# Sheet1.net
KiCad netlist of a schematic drawn in Altium Designer
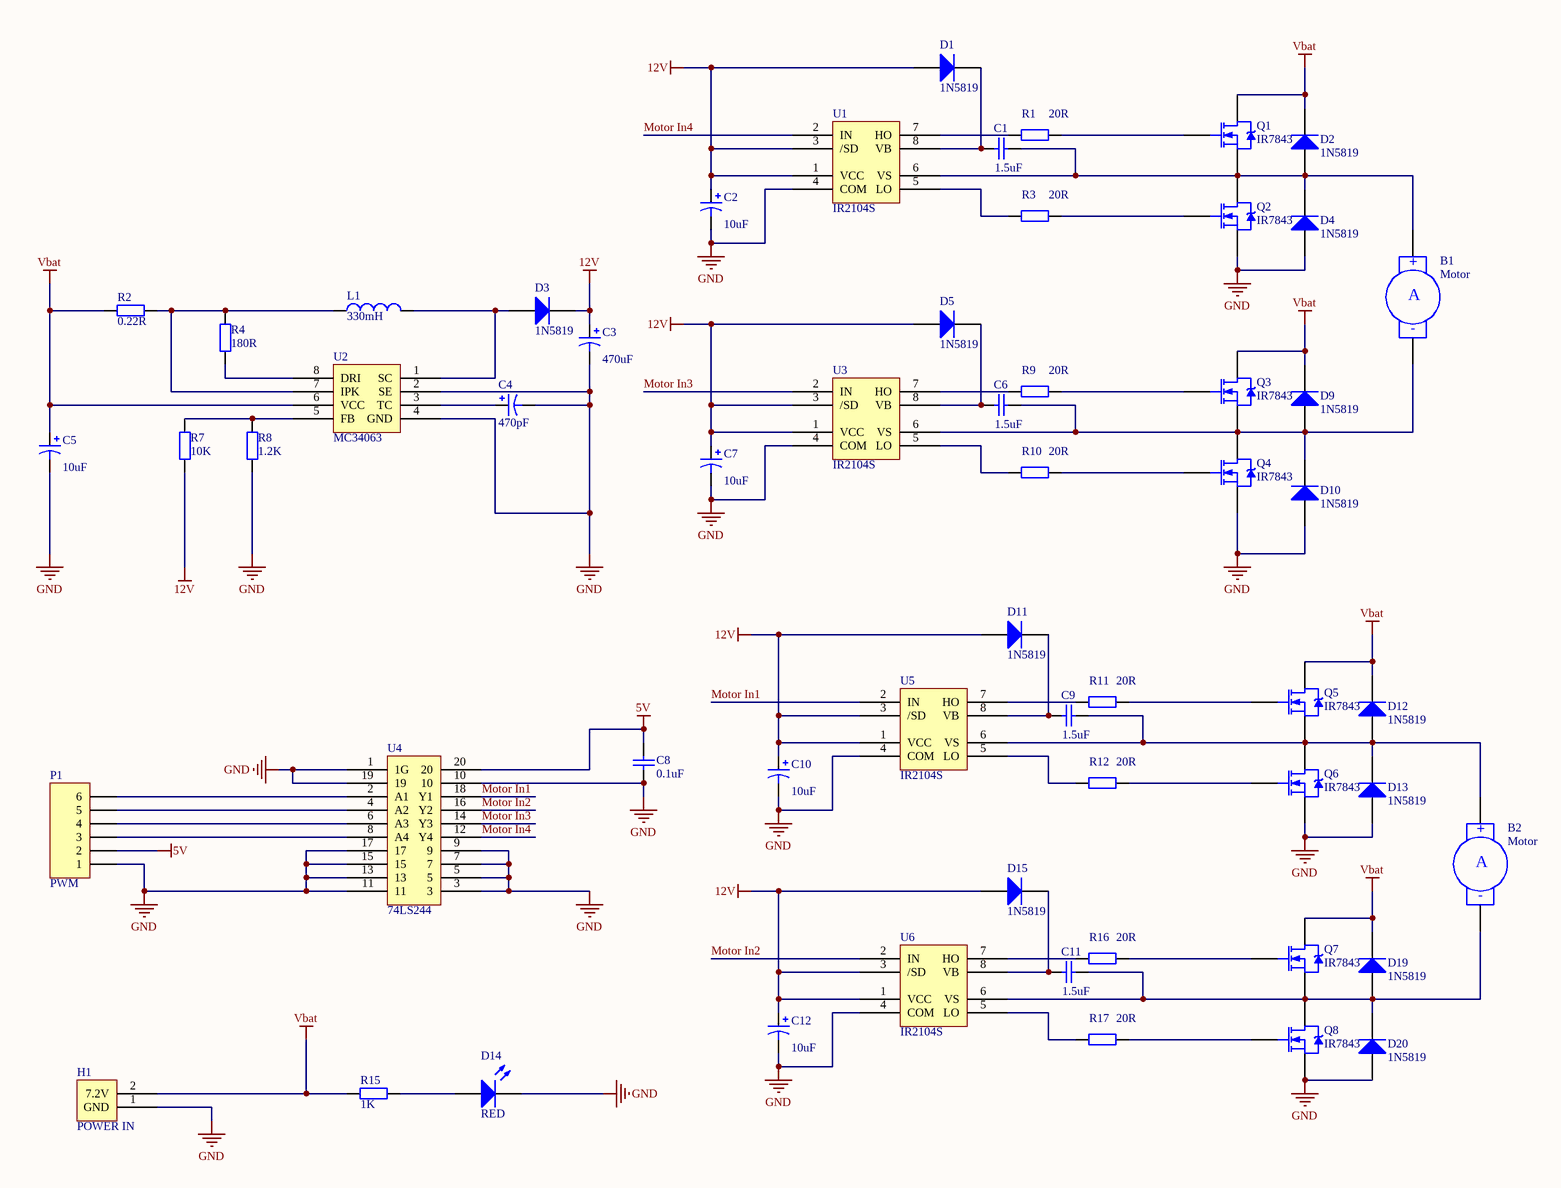
[diagram p0: Sheet1.SchDoc]

(export (version "E")
  (design (tool "Eeschema 10.0.6"))
  (components
    (comp (ref "B1")
      (value "Motor")
      (footprint "KF301-2P")
      (description "Servo Motor")
      (fields (field (name "PUBLISHER") "Altium Limited"))
      (libsource (lib "Miscellaneous Devices") (part "Motor Servo"))
    )
    (comp (ref "B2")
      (value "Motor")
      (footprint "KF301-2P")
      (description "Servo Motor")
      (fields (field (name "PUBLISHER") "Altium Limited"))
      (libsource (lib "Miscellaneous Devices") (part "Motor Servo"))
    )
    (comp (ref "C1")
      (value "1.5uF")
      (footprint "0805(2012)")
      (description "Capacitor")
      (fields (field (name "Comment") "Cap") (field (name "PUBLISHER") "Altium Limited"))
      (libsource (lib "Miscellaneous Devices") (part "Cap"))
    )
    (comp (ref "C2")
      (value "10uF")
      (footprint "SOD-323(0805)")
      (description "Polarized Capacitor (Radial)")
      (fields (field (name "Comment") "Cap Pol1") (field (name "PUBLISHER") "Altium Limited"))
      (libsource (lib "Miscellaneous Devices") (part "Cap Pol1"))
    )
    (comp (ref "C3")
      (value "470uF")
      (footprint "RB5-10.5")
      (description "Polarized Capacitor (Radial)")
      (fields (field (name "Comment") "Cap Pol1") (field (name "PUBLISHER") "Altium Limited"))
      (libsource (lib "Miscellaneous Devices") (part "Cap Pol1"))
    )
    (comp (ref "C4")
      (value "470pF")
      (footprint "SOD-323(0805)")
      (description "Polarized Capacitor (Radial)")
      (fields (field (name "Comment") "Cap Pol1") (field (name "PUBLISHER") "Altium Limited"))
      (libsource (lib "Miscellaneous Devices") (part "Cap Pol1"))
    )
    (comp (ref "C5")
      (value "10uF")
      (footprint "SOD-323(0805)")
      (description "Polarized Capacitor (Radial)")
      (fields (field (name "Comment") "Cap Pol1") (field (name "PUBLISHER") "Altium Limited"))
      (libsource (lib "Miscellaneous Devices") (part "Cap Pol1"))
    )
    (comp (ref "C6")
      (value "1.5uF")
      (footprint "0805(2012)")
      (description "Capacitor")
      (fields (field (name "Comment") "Cap") (field (name "PUBLISHER") "Altium Limited"))
      (libsource (lib "Miscellaneous Devices") (part "Cap"))
    )
    (comp (ref "C7")
      (value "10uF")
      (footprint "SOD-323(0805)")
      (description "Polarized Capacitor (Radial)")
      (fields (field (name "Comment") "Cap Pol1") (field (name "PUBLISHER") "Altium Limited"))
      (libsource (lib "Miscellaneous Devices") (part "Cap Pol1"))
    )
    (comp (ref "C8")
      (value "0.1uF")
      (footprint "0805(2012)")
      (description "Capacitor")
      (fields (field (name "Comment") "Cap") (field (name "PUBLISHER") "Altium Limited"))
      (libsource (lib "LY") (part "Cap"))
    )
    (comp (ref "C9")
      (value "1.5uF")
      (footprint "0805(2012)")
      (description "Capacitor")
      (fields (field (name "Comment") "Cap") (field (name "PUBLISHER") "Altium Limited"))
      (libsource (lib "Miscellaneous Devices") (part "Cap"))
    )
    (comp (ref "C10")
      (value "10uF")
      (footprint "SOD-323(0805)")
      (description "Polarized Capacitor (Radial)")
      (fields (field (name "Comment") "Cap Pol1") (field (name "PUBLISHER") "Altium Limited"))
      (libsource (lib "Miscellaneous Devices") (part "Cap Pol1"))
    )
    (comp (ref "C11")
      (value "1.5uF")
      (footprint "0805(2012)")
      (description "Capacitor")
      (fields (field (name "Comment") "Cap") (field (name "PUBLISHER") "Altium Limited"))
      (libsource (lib "Miscellaneous Devices") (part "Cap"))
    )
    (comp (ref "C12")
      (value "10uF")
      (footprint "SOD-323(0805)")
      (description "Polarized Capacitor (Radial)")
      (fields (field (name "Comment") "Cap Pol1") (field (name "PUBLISHER") "Altium Limited"))
      (libsource (lib "Miscellaneous Devices") (part "Cap Pol1"))
    )
    (comp (ref "D1")
      (value "1N5819")
      (footprint "0805(2012)")
      (description "Silicon Epitaxial Planar Diode for Various Detector, Modulator, Demodulator")
      (fields (field (name "PUBLISHER") "Altium Limited"))
      (libsource (lib "Renesas Diode") (part "1N4148"))
    )
    (comp (ref "D2")
      (value "1N5819")
      (footprint "0805(2012)")
      (description "Silicon Epitaxial Planar Diode for Various Detector, Modulator, Demodulator")
      (fields (field (name "PUBLISHER") "Altium Limited"))
      (libsource (lib "Renesas Diode") (part "1N4148"))
    )
    (comp (ref "D3")
      (value "1N5819")
      (footprint "0805(2012)")
      (description "Silicon Epitaxial Planar Diode for Various Detector, Modulator, Demodulator")
      (fields (field (name "PUBLISHER") "Altium Limited"))
      (libsource (lib "Renesas Diode") (part "1N4148"))
    )
    (comp (ref "D4")
      (value "1N5819")
      (footprint "0805(2012)")
      (description "Silicon Epitaxial Planar Diode for Various Detector, Modulator, Demodulator")
      (fields (field (name "PUBLISHER") "Altium Limited"))
      (libsource (lib "Renesas Diode") (part "1N4148"))
    )
    (comp (ref "D5")
      (value "1N5819")
      (footprint "0805(2012)")
      (description "Silicon Epitaxial Planar Diode for Various Detector, Modulator, Demodulator")
      (fields (field (name "PUBLISHER") "Altium Limited"))
      (libsource (lib "Renesas Diode") (part "1N4148"))
    )
    (comp (ref "D9")
      (value "1N5819")
      (footprint "0805(2012)")
      (description "Silicon Epitaxial Planar Diode for Various Detector, Modulator, Demodulator")
      (fields (field (name "PUBLISHER") "Altium Limited"))
      (libsource (lib "Renesas Diode") (part "1N4148"))
    )
    (comp (ref "D10")
      (value "1N5819")
      (footprint "0805(2012)")
      (description "Silicon Epitaxial Planar Diode for Various Detector, Modulator, Demodulator")
      (fields (field (name "PUBLISHER") "Altium Limited"))
      (libsource (lib "Renesas Diode") (part "1N4148"))
    )
    (comp (ref "D11")
      (value "1N5819")
      (footprint "0805(2012)")
      (description "Silicon Epitaxial Planar Diode for Various Detector, Modulator, Demodulator")
      (fields (field (name "PUBLISHER") "Altium Limited"))
      (libsource (lib "Renesas Diode") (part "1N4148"))
    )
    (comp (ref "D12")
      (value "1N5819")
      (footprint "0805(2012)")
      (description "Silicon Epitaxial Planar Diode for Various Detector, Modulator, Demodulator")
      (fields (field (name "PUBLISHER") "Altium Limited"))
      (libsource (lib "Renesas Diode") (part "1N4148"))
    )
    (comp (ref "D13")
      (value "1N5819")
      (footprint "0805(2012)")
      (description "Silicon Epitaxial Planar Diode for Various Detector, Modulator, Demodulator")
      (fields (field (name "PUBLISHER") "Altium Limited"))
      (libsource (lib "Renesas Diode") (part "1N4148"))
    )
    (comp (ref "D14")
      (value "RED")
      (footprint "0805LED")
      (description "Typical RED, GREEN, YELLOW, AMBER GaAs LED")
      (fields (field (name "PUBLISHER") "Altium Limited"))
      (libsource (lib "LY") (part "LED2"))
    )
    (comp (ref "D15")
      (value "1N5819")
      (footprint "0805(2012)")
      (description "Silicon Epitaxial Planar Diode for Various Detector, Modulator, Demodulator")
      (fields (field (name "PUBLISHER") "Altium Limited"))
      (libsource (lib "Renesas Diode") (part "1N4148"))
    )
    (comp (ref "D19")
      (value "1N5819")
      (footprint "0805(2012)")
      (description "Silicon Epitaxial Planar Diode for Various Detector, Modulator, Demodulator")
      (fields (field (name "PUBLISHER") "Altium Limited"))
      (libsource (lib "Renesas Diode") (part "1N4148"))
    )
    (comp (ref "D20")
      (value "1N5819")
      (footprint "0805(2012)")
      (description "Silicon Epitaxial Planar Diode for Various Detector, Modulator, Demodulator")
      (fields (field (name "PUBLISHER") "Altium Limited"))
      (libsource (lib "Renesas Diode") (part "1N4148"))
    )
    (comp (ref "H1")
      (value "POWER IN")
      (footprint "KF301-2P")
      (libsource (lib "MOS motor") (part "POWER IN"))
    )
    (comp (ref "L1")
      (value "330mH")
      (footprint "电感10*12")
      (description "Inductor")
      (fields (field (name "PUBLISHER") "Altium Limited"))
      (libsource (lib "Miscellaneous Devices") (part "Inductor"))
    )
    (comp (ref "P1")
      (value "PWM")
      (footprint "HDR1X6")
      (description "Header, 6-Pin")
      (fields (field (name "PUBLISHER") "Altium Limited"))
      (libsource (lib "Miscellaneous Connectors") (part "Header 6"))
    )
    (comp (ref "Q1")
      (value "IR7843")
      (footprint "LR7843")
      (description "N-Channel Power MOSFET")
      (fields (field (name "PUBLISHER") "Altium Limited"))
      (libsource (lib "PowerIn") (part "IR7843"))
    )
    (comp (ref "Q2")
      (value "IR7843")
      (footprint "LR7843")
      (description "N-Channel Power MOSFET")
      (fields (field (name "PUBLISHER") "Altium Limited"))
      (libsource (lib "PowerIn") (part "IR7843"))
    )
    (comp (ref "Q3")
      (value "IR7843")
      (footprint "LR7843")
      (description "N-Channel Power MOSFET")
      (fields (field (name "PUBLISHER") "Altium Limited"))
      (libsource (lib "PowerIn") (part "IR7843"))
    )
    (comp (ref "Q4")
      (value "IR7843")
      (footprint "LR7843")
      (description "N-Channel Power MOSFET")
      (fields (field (name "PUBLISHER") "Altium Limited"))
      (libsource (lib "PowerIn") (part "IR7843"))
    )
    (comp (ref "Q5")
      (value "IR7843")
      (footprint "LR7843")
      (description "N-Channel Power MOSFET")
      (fields (field (name "PUBLISHER") "Altium Limited"))
      (libsource (lib "PowerIn") (part "IR7843"))
    )
    (comp (ref "Q6")
      (value "IR7843")
      (footprint "LR7843")
      (description "N-Channel Power MOSFET")
      (fields (field (name "PUBLISHER") "Altium Limited"))
      (libsource (lib "PowerIn") (part "IR7843"))
    )
    (comp (ref "Q7")
      (value "IR7843")
      (footprint "LR7843")
      (description "N-Channel Power MOSFET")
      (fields (field (name "PUBLISHER") "Altium Limited"))
      (libsource (lib "PowerIn") (part "IR7843"))
    )
    (comp (ref "Q8")
      (value "IR7843")
      (footprint "LR7843")
      (description "N-Channel Power MOSFET")
      (fields (field (name "PUBLISHER") "Altium Limited"))
      (libsource (lib "PowerIn") (part "IR7843"))
    )
    (comp (ref "R1")
      (value "20R")
      (footprint "0805(2012)")
      (description "Resistor")
      (fields (field (name "Comment") "Res2") (field (name "PUBLISHER") "Altium Limited"))
      (libsource (lib "altium-import") (part "root_0_Res2_"))
    )
    (comp (ref "R2")
      (value "0.22R")
      (footprint "1206(3216)")
      (description "Resistor")
      (fields (field (name "Comment") "Res2") (field (name "PUBLISHER") "Altium Limited"))
      (libsource (lib "altium-import") (part "root_2_Res2_"))
    )
    (comp (ref "R3")
      (value "20R")
      (footprint "0805(2012)")
      (description "Resistor")
      (fields (field (name "Comment") "Res2") (field (name "PUBLISHER") "Altium Limited"))
      (libsource (lib "altium-import") (part "root_0_Res2_"))
    )
    (comp (ref "R4")
      (value "180R")
      (footprint "0805(2012)")
      (description "Resistor")
      (fields (field (name "Comment") "Res2") (field (name "PUBLISHER") "Altium Limited"))
      (libsource (lib "LY") (part "Res2"))
    )
    (comp (ref "R7")
      (value "10K")
      (footprint "0805(2012)")
      (description "Resistor")
      (fields (field (name "Comment") "Res2") (field (name "PUBLISHER") "Altium Limited"))
      (libsource (lib "LY") (part "Res2"))
    )
    (comp (ref "R8")
      (value "1.2K")
      (footprint "0805(2012)")
      (description "Resistor")
      (fields (field (name "Comment") "Res2") (field (name "PUBLISHER") "Altium Limited"))
      (libsource (lib "LY") (part "Res2"))
    )
    (comp (ref "R9")
      (value "20R")
      (footprint "0805(2012)")
      (description "Resistor")
      (fields (field (name "Comment") "Res2") (field (name "PUBLISHER") "Altium Limited"))
      (libsource (lib "altium-import") (part "root_0_Res2_"))
    )
    (comp (ref "R10")
      (value "20R")
      (footprint "0805(2012)")
      (description "Resistor")
      (fields (field (name "Comment") "Res2") (field (name "PUBLISHER") "Altium Limited"))
      (libsource (lib "altium-import") (part "root_0_Res2_"))
    )
    (comp (ref "R11")
      (value "20R")
      (footprint "0805(2012)")
      (description "Resistor")
      (fields (field (name "Comment") "Res2") (field (name "PUBLISHER") "Altium Limited"))
      (libsource (lib "altium-import") (part "root_0_Res2_"))
    )
    (comp (ref "R12")
      (value "20R")
      (footprint "0805(2012)")
      (description "Resistor")
      (fields (field (name "Comment") "Res2") (field (name "PUBLISHER") "Altium Limited"))
      (libsource (lib "altium-import") (part "root_0_Res2_"))
    )
    (comp (ref "R15")
      (value "1K")
      (footprint "0805(2012)")
      (description "Resistor")
      (fields (field (name "Comment") "Res2") (field (name "PUBLISHER") "Altium Limited"))
      (libsource (lib "") (part "Res2_1"))
    )
    (comp (ref "R16")
      (value "20R")
      (footprint "0805(2012)")
      (description "Resistor")
      (fields (field (name "Comment") "Res2") (field (name "PUBLISHER") "Altium Limited"))
      (libsource (lib "altium-import") (part "root_0_Res2_"))
    )
    (comp (ref "R17")
      (value "20R")
      (footprint "0805(2012)")
      (description "Resistor")
      (fields (field (name "Comment") "Res2") (field (name "PUBLISHER") "Altium Limited"))
      (libsource (lib "altium-import") (part "root_0_Res2_"))
    )
    (comp (ref "U1") (value "IR2104S") (footprint "IR2104S") (libsource (lib "LY") (part "IR2104S")))
    (comp (ref "U2") (value "MC34063") (footprint "MC34063") (libsource (lib "LY") (part "MC34063")))
    (comp (ref "U3") (value "IR2104S") (footprint "IR2104S") (libsource (lib "LY") (part "IR2104S")))
    (comp (ref "U4") (value "74LS244") (footprint "74ls244DA") (libsource (lib "LY") (part "74LS244")))
    (comp (ref "U5") (value "IR2104S") (footprint "IR2104S") (libsource (lib "LY") (part "IR2104S")))
    (comp (ref "U6") (value "IR2104S") (footprint "IR2104S") (libsource (lib "LY") (part "IR2104S")))
  )
  (nets
    (net (code "1") (name "/Motor In1") (class "Default")
      (node (ref "U4") (pin "18") (pinfunction "Y1_18") (pintype "passive"))
      (node (ref "U5") (pin "2") (pinfunction "IN_2") (pintype "passive"))
    )
    (net (code "2") (name "/Motor In2") (class "Default")
      (node (ref "U4") (pin "16") (pinfunction "Y2_16") (pintype "passive"))
      (node (ref "U6") (pin "2") (pinfunction "IN_2") (pintype "passive"))
    )
    (net (code "3") (name "/Motor In3") (class "Default")
      (node (ref "U3") (pin "2") (pinfunction "IN_2") (pintype "passive"))
      (node (ref "U4") (pin "14") (pinfunction "Y3_14") (pintype "passive"))
    )
    (net (code "4") (name "/Motor In4") (class "Default")
      (node (ref "U1") (pin "2") (pinfunction "IN_2") (pintype "passive"))
      (node (ref "U4") (pin "12") (pinfunction "Y4_12") (pintype "passive"))
    )
    (net (code "5") (name "5V") (class "Default")
      (node (ref "C8") (pin "2") (pinfunction "2_2") (pintype "passive"))
      (node (ref "P1") (pin "2") (pinfunction "2_2") (pintype "passive"))
      (node (ref "U4") (pin "20") (pinfunction "20_20") (pintype "passive"))
    )
    (net (code "6") (name "12V") (class "Default")
      (node (ref "C10") (pin "1") (pinfunction "1_1") (pintype "passive"))
      (node (ref "C12") (pin "1") (pinfunction "1_1") (pintype "passive"))
      (node (ref "C2") (pin "1") (pinfunction "1_1") (pintype "passive"))
      (node (ref "C3") (pin "1") (pinfunction "1_1") (pintype "passive"))
      (node (ref "C7") (pin "1") (pinfunction "1_1") (pintype "passive"))
      (node (ref "D1") (pin "2") (pinfunction "A_2") (pintype "passive"))
      (node (ref "D11") (pin "2") (pinfunction "A_2") (pintype "passive"))
      (node (ref "D15") (pin "2") (pinfunction "A_2") (pintype "passive"))
      (node (ref "D3") (pin "1") (pinfunction "K_1") (pintype "passive"))
      (node (ref "D5") (pin "2") (pinfunction "A_2") (pintype "passive"))
      (node (ref "R7") (pin "1") (pinfunction "1_1") (pintype "passive"))
      (node (ref "U1") (pin "1") (pinfunction "VCC_1") (pintype "passive"))
      (node (ref "U1") (pin "3") (pinfunction "/SD_3") (pintype "passive"))
      (node (ref "U3") (pin "1") (pinfunction "VCC_1") (pintype "passive"))
      (node (ref "U3") (pin "3") (pinfunction "/SD_3") (pintype "passive"))
      (node (ref "U5") (pin "1") (pinfunction "VCC_1") (pintype "passive"))
      (node (ref "U5") (pin "3") (pinfunction "/SD_3") (pintype "passive"))
      (node (ref "U6") (pin "1") (pinfunction "VCC_1") (pintype "passive"))
      (node (ref "U6") (pin "3") (pinfunction "/SD_3") (pintype "passive"))
    )
    (net (code "7") (name "GND") (class "Default")
      (node (ref "C10") (pin "2") (pinfunction "2_2") (pintype "passive"))
      (node (ref "C12") (pin "2") (pinfunction "2_2") (pintype "passive"))
      (node (ref "C2") (pin "2") (pinfunction "2_2") (pintype "passive"))
      (node (ref "C3") (pin "2") (pinfunction "2_2") (pintype "passive"))
      (node (ref "C4") (pin "2") (pinfunction "2_2") (pintype "passive"))
      (node (ref "C5") (pin "2") (pinfunction "2_2") (pintype "passive"))
      (node (ref "C7") (pin "2") (pinfunction "2_2") (pintype "passive"))
      (node (ref "C8") (pin "1") (pinfunction "1_1") (pintype "passive"))
      (node (ref "D10") (pin "2") (pinfunction "A_2") (pintype "passive"))
      (node (ref "D13") (pin "2") (pinfunction "A_2") (pintype "passive"))
      (node (ref "D14") (pin "2") (pinfunction "K_2") (pintype "passive"))
      (node (ref "D20") (pin "2") (pinfunction "A_2") (pintype "passive"))
      (node (ref "D4") (pin "2") (pinfunction "A_2") (pintype "passive"))
      (node (ref "H1") (pin "1") (pinfunction "GND_1") (pintype "passive"))
      (node (ref "P1") (pin "1") (pinfunction "1_1") (pintype "passive"))
      (node (ref "Q2") (pin "3") (pinfunction "S_3") (pintype "passive"))
      (node (ref "Q4") (pin "3") (pinfunction "S_3") (pintype "passive"))
      (node (ref "Q6") (pin "3") (pinfunction "S_3") (pintype "passive"))
      (node (ref "Q8") (pin "3") (pinfunction "S_3") (pintype "passive"))
      (node (ref "R8") (pin "1") (pinfunction "1_1") (pintype "passive"))
      (node (ref "U1") (pin "4") (pinfunction "COM_4") (pintype "passive"))
      (node (ref "U2") (pin "2") (pinfunction "SE_2") (pintype "passive"))
      (node (ref "U2") (pin "4") (pinfunction "GND_4") (pintype "passive"))
      (node (ref "U3") (pin "4") (pinfunction "COM_4") (pintype "passive"))
      (node (ref "U4") (pin "1") (pinfunction "1G_1") (pintype "passive"))
      (node (ref "U4") (pin "10") (pinfunction "10_10") (pintype "passive"))
      (node (ref "U4") (pin "11") (pinfunction "11_11") (pintype "passive"))
      (node (ref "U4") (pin "13") (pinfunction "13_13") (pintype "passive"))
      (node (ref "U4") (pin "15") (pinfunction "15_15") (pintype "passive"))
      (node (ref "U4") (pin "17") (pinfunction "17_17") (pintype "passive"))
      (node (ref "U4") (pin "19") (pinfunction "19_19") (pintype "passive"))
      (node (ref "U4") (pin "3") (pinfunction "3_3") (pintype "passive"))
      (node (ref "U4") (pin "5") (pinfunction "5_5") (pintype "passive"))
      (node (ref "U4") (pin "7") (pinfunction "7_7") (pintype "passive"))
      (node (ref "U4") (pin "9") (pinfunction "9_9") (pintype "passive"))
      (node (ref "U5") (pin "4") (pinfunction "COM_4") (pintype "passive"))
      (node (ref "U6") (pin "4") (pinfunction "COM_4") (pintype "passive"))
    )
    (net (code "8") (name "Net-(B1-+)") (class "Default")
      (node (ref "B1") (pin "1") (pinfunction "+_1") (pintype "passive"))
      (node (ref "C1") (pin "2") (pinfunction "2_2") (pintype "passive"))
      (node (ref "D2") (pin "2") (pinfunction "A_2") (pintype "passive"))
      (node (ref "D4") (pin "1") (pinfunction "K_1") (pintype "passive"))
      (node (ref "Q1") (pin "3") (pinfunction "S_3") (pintype "passive"))
      (node (ref "Q2") (pin "2") (pinfunction "D_2") (pintype "passive"))
      (node (ref "U1") (pin "6") (pinfunction "VS_6") (pintype "passive"))
    )
    (net (code "9") (name "Net-(B1--)") (class "Default")
      (node (ref "B1") (pin "2") (pinfunction "-_2") (pintype "passive"))
      (node (ref "C6") (pin "2") (pinfunction "2_2") (pintype "passive"))
      (node (ref "D10") (pin "1") (pinfunction "K_1") (pintype "passive"))
      (node (ref "D9") (pin "2") (pinfunction "A_2") (pintype "passive"))
      (node (ref "Q3") (pin "3") (pinfunction "S_3") (pintype "passive"))
      (node (ref "Q4") (pin "2") (pinfunction "D_2") (pintype "passive"))
      (node (ref "U3") (pin "6") (pinfunction "VS_6") (pintype "passive"))
    )
    (net (code "10") (name "Net-(B2-+)") (class "Default")
      (node (ref "B2") (pin "1") (pinfunction "+_1") (pintype "passive"))
      (node (ref "C9") (pin "2") (pinfunction "2_2") (pintype "passive"))
      (node (ref "D12") (pin "2") (pinfunction "A_2") (pintype "passive"))
      (node (ref "D13") (pin "1") (pinfunction "K_1") (pintype "passive"))
      (node (ref "Q5") (pin "3") (pinfunction "S_3") (pintype "passive"))
      (node (ref "Q6") (pin "2") (pinfunction "D_2") (pintype "passive"))
      (node (ref "U5") (pin "6") (pinfunction "VS_6") (pintype "passive"))
    )
    (net (code "11") (name "Net-(B2--)") (class "Default")
      (node (ref "B2") (pin "2") (pinfunction "-_2") (pintype "passive"))
      (node (ref "C11") (pin "2") (pinfunction "2_2") (pintype "passive"))
      (node (ref "D19") (pin "2") (pinfunction "A_2") (pintype "passive"))
      (node (ref "D20") (pin "1") (pinfunction "K_1") (pintype "passive"))
      (node (ref "Q7") (pin "3") (pinfunction "S_3") (pintype "passive"))
      (node (ref "Q8") (pin "2") (pinfunction "D_2") (pintype "passive"))
      (node (ref "U6") (pin "6") (pinfunction "VS_6") (pintype "passive"))
    )
    (net (code "12") (name "Net-(D1-K)") (class "Default")
      (node (ref "C1") (pin "1") (pinfunction "1_1") (pintype "passive"))
      (node (ref "D1") (pin "1") (pinfunction "K_1") (pintype "passive"))
      (node (ref "U1") (pin "8") (pinfunction "VB_8") (pintype "passive"))
    )
    (net (code "13") (name "Net-(D3-A)") (class "Default")
      (node (ref "D3") (pin "2") (pinfunction "A_2") (pintype "passive"))
      (node (ref "L1") (pin "2") (pinfunction "2_2") (pintype "passive"))
      (node (ref "U2") (pin "1") (pinfunction "SC_1") (pintype "passive"))
    )
    (net (code "14") (name "Net-(D5-K)") (class "Default")
      (node (ref "C6") (pin "1") (pinfunction "1_1") (pintype "passive"))
      (node (ref "D5") (pin "1") (pinfunction "K_1") (pintype "passive"))
      (node (ref "U3") (pin "8") (pinfunction "VB_8") (pintype "passive"))
    )
    (net (code "15") (name "Net-(D11-K)") (class "Default")
      (node (ref "C9") (pin "1") (pinfunction "1_1") (pintype "passive"))
      (node (ref "D11") (pin "1") (pinfunction "K_1") (pintype "passive"))
      (node (ref "U5") (pin "8") (pinfunction "VB_8") (pintype "passive"))
    )
    (net (code "16") (name "Net-(D14-A)") (class "Default")
      (node (ref "D14") (pin "1") (pinfunction "A_1") (pintype "passive"))
      (node (ref "R15") (pin "2") (pinfunction "2_2") (pintype "passive"))
    )
    (net (code "17") (name "Net-(D15-K)") (class "Default")
      (node (ref "C11") (pin "1") (pinfunction "1_1") (pintype "passive"))
      (node (ref "D15") (pin "1") (pinfunction "K_1") (pintype "passive"))
      (node (ref "U6") (pin "8") (pinfunction "VB_8") (pintype "passive"))
    )
    (net (code "18") (name "Net-(Q1-G)") (class "Default")
      (node (ref "Q1") (pin "1") (pinfunction "G_1") (pintype "passive"))
      (node (ref "R1") (pin "2") (pinfunction "2_2") (pintype "passive"))
    )
    (net (code "19") (name "Net-(Q2-G)") (class "Default")
      (node (ref "Q2") (pin "1") (pinfunction "G_1") (pintype "passive"))
      (node (ref "R3") (pin "2") (pinfunction "2_2") (pintype "passive"))
    )
    (net (code "20") (name "Net-(Q3-G)") (class "Default")
      (node (ref "Q3") (pin "1") (pinfunction "G_1") (pintype "passive"))
      (node (ref "R9") (pin "2") (pinfunction "2_2") (pintype "passive"))
    )
    (net (code "21") (name "Net-(Q4-G)") (class "Default")
      (node (ref "Q4") (pin "1") (pinfunction "G_1") (pintype "passive"))
      (node (ref "R10") (pin "2") (pinfunction "2_2") (pintype "passive"))
    )
    (net (code "22") (name "Net-(Q5-G)") (class "Default")
      (node (ref "Q5") (pin "1") (pinfunction "G_1") (pintype "passive"))
      (node (ref "R11") (pin "2") (pinfunction "2_2") (pintype "passive"))
    )
    (net (code "23") (name "Net-(Q6-G)") (class "Default")
      (node (ref "Q6") (pin "1") (pinfunction "G_1") (pintype "passive"))
      (node (ref "R12") (pin "2") (pinfunction "2_2") (pintype "passive"))
    )
    (net (code "24") (name "Net-(Q7-G)") (class "Default")
      (node (ref "Q7") (pin "1") (pinfunction "G_1") (pintype "passive"))
      (node (ref "R16") (pin "2") (pinfunction "2_2") (pintype "passive"))
    )
    (net (code "25") (name "Net-(Q8-G)") (class "Default")
      (node (ref "Q8") (pin "1") (pinfunction "G_1") (pintype "passive"))
      (node (ref "R17") (pin "2") (pinfunction "2_2") (pintype "passive"))
    )
    (net (code "26") (name "Net-(U1-HO)") (class "Default")
      (node (ref "R1") (pin "1") (pinfunction "1_1") (pintype "passive"))
      (node (ref "U1") (pin "7") (pinfunction "HO_7") (pintype "passive"))
    )
    (net (code "27") (name "Net-(U1-LO)") (class "Default")
      (node (ref "R3") (pin "1") (pinfunction "1_1") (pintype "passive"))
      (node (ref "U1") (pin "5") (pinfunction "LO_5") (pintype "passive"))
    )
    (net (code "28") (name "Net-(U2-DRI)") (class "Default")
      (node (ref "R4") (pin "1") (pinfunction "1_1") (pintype "passive"))
      (node (ref "U2") (pin "8") (pinfunction "DRI_8") (pintype "passive"))
    )
    (net (code "29") (name "Net-(U2-FB)") (class "Default")
      (node (ref "R7") (pin "2") (pinfunction "2_2") (pintype "passive"))
      (node (ref "R8") (pin "2") (pinfunction "2_2") (pintype "passive"))
      (node (ref "U2") (pin "5") (pinfunction "FB_5") (pintype "passive"))
    )
    (net (code "30") (name "Net-(U2-IPK)") (class "Default")
      (node (ref "L1") (pin "1") (pinfunction "1_1") (pintype "passive"))
      (node (ref "R2") (pin "1") (pinfunction "1_1") (pintype "passive"))
      (node (ref "R4") (pin "2") (pinfunction "2_2") (pintype "passive"))
      (node (ref "U2") (pin "7") (pinfunction "IPK_7") (pintype "passive"))
    )
    (net (code "31") (name "Net-(U2-TC)") (class "Default")
      (node (ref "C4") (pin "1") (pinfunction "1_1") (pintype "passive"))
      (node (ref "U2") (pin "3") (pinfunction "TC_3") (pintype "passive"))
    )
    (net (code "32") (name "Net-(U3-HO)") (class "Default")
      (node (ref "R9") (pin "1") (pinfunction "1_1") (pintype "passive"))
      (node (ref "U3") (pin "7") (pinfunction "HO_7") (pintype "passive"))
    )
    (net (code "33") (name "Net-(U3-LO)") (class "Default")
      (node (ref "R10") (pin "1") (pinfunction "1_1") (pintype "passive"))
      (node (ref "U3") (pin "5") (pinfunction "LO_5") (pintype "passive"))
    )
    (net (code "34") (name "Net-(U4-A1)") (class "Default")
      (node (ref "P1") (pin "6") (pinfunction "6_6") (pintype "passive"))
      (node (ref "U4") (pin "2") (pinfunction "A1_2") (pintype "passive"))
    )
    (net (code "35") (name "Net-(U4-A2)") (class "Default")
      (node (ref "P1") (pin "5") (pinfunction "5_5") (pintype "passive"))
      (node (ref "U4") (pin "4") (pinfunction "A2_4") (pintype "passive"))
    )
    (net (code "36") (name "Net-(U4-A3)") (class "Default")
      (node (ref "P1") (pin "4") (pinfunction "4_4") (pintype "passive"))
      (node (ref "U4") (pin "6") (pinfunction "A3_6") (pintype "passive"))
    )
    (net (code "37") (name "Net-(U4-A4)") (class "Default")
      (node (ref "P1") (pin "3") (pinfunction "3_3") (pintype "passive"))
      (node (ref "U4") (pin "8") (pinfunction "A4_8") (pintype "passive"))
    )
    (net (code "38") (name "Net-(U5-HO)") (class "Default")
      (node (ref "R11") (pin "1") (pinfunction "1_1") (pintype "passive"))
      (node (ref "U5") (pin "7") (pinfunction "HO_7") (pintype "passive"))
    )
    (net (code "39") (name "Net-(U5-LO)") (class "Default")
      (node (ref "R12") (pin "1") (pinfunction "1_1") (pintype "passive"))
      (node (ref "U5") (pin "5") (pinfunction "LO_5") (pintype "passive"))
    )
    (net (code "40") (name "Net-(U6-HO)") (class "Default")
      (node (ref "R16") (pin "1") (pinfunction "1_1") (pintype "passive"))
      (node (ref "U6") (pin "7") (pinfunction "HO_7") (pintype "passive"))
    )
    (net (code "41") (name "Net-(U6-LO)") (class "Default")
      (node (ref "R17") (pin "1") (pinfunction "1_1") (pintype "passive"))
      (node (ref "U6") (pin "5") (pinfunction "LO_5") (pintype "passive"))
    )
    (net (code "42") (name "Vbat") (class "Default")
      (node (ref "C5") (pin "1") (pinfunction "1_1") (pintype "passive"))
      (node (ref "D12") (pin "1") (pinfunction "K_1") (pintype "passive"))
      (node (ref "D19") (pin "1") (pinfunction "K_1") (pintype "passive"))
      (node (ref "D2") (pin "1") (pinfunction "K_1") (pintype "passive"))
      (node (ref "D9") (pin "1") (pinfunction "K_1") (pintype "passive"))
      (node (ref "H1") (pin "2") (pinfunction "7.2V_2") (pintype "passive"))
      (node (ref "Q1") (pin "2") (pinfunction "D_2") (pintype "passive"))
      (node (ref "Q3") (pin "2") (pinfunction "D_2") (pintype "passive"))
      (node (ref "Q5") (pin "2") (pinfunction "D_2") (pintype "passive"))
      (node (ref "Q7") (pin "2") (pinfunction "D_2") (pintype "passive"))
      (node (ref "R15") (pin "1") (pinfunction "1_1") (pintype "passive"))
      (node (ref "R2") (pin "2") (pinfunction "2_2") (pintype "passive"))
      (node (ref "U2") (pin "6") (pinfunction "VCC_6") (pintype "passive"))
    )
  )
)
